# BUS.net
KiCad netlist of a schematic drawn in Altium Designer
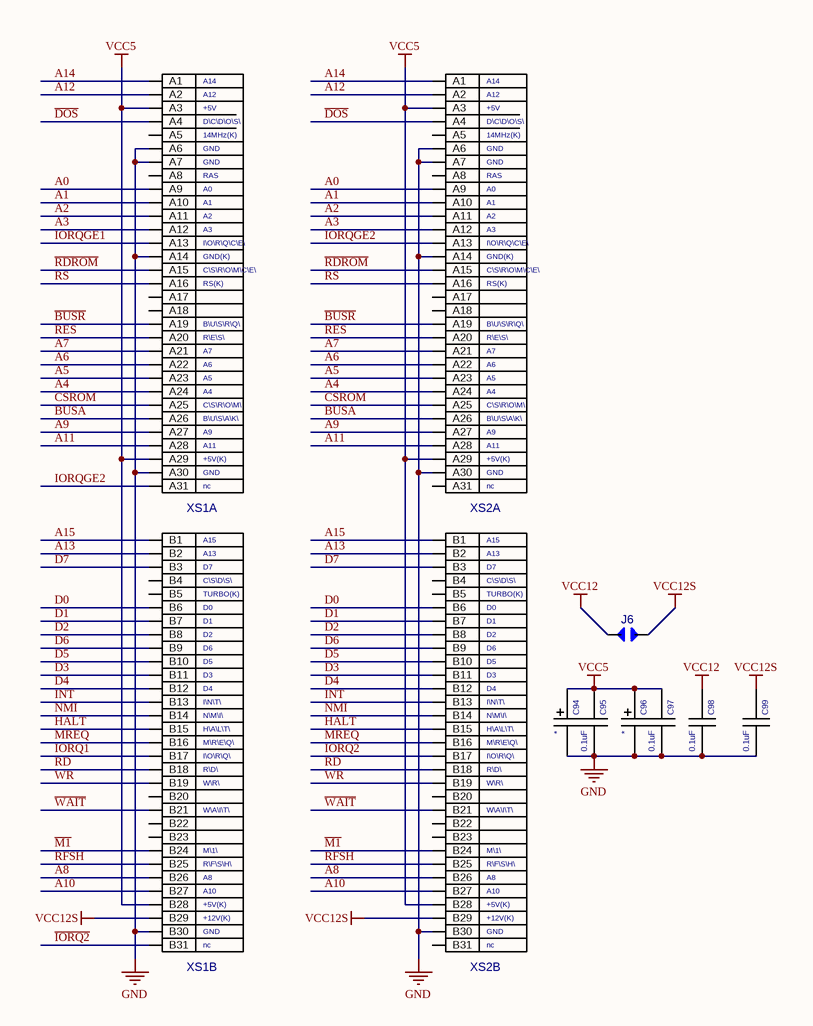
[diagram p0: BUS.SchDoc]

(export (version "E")
  (design (tool "Eeschema 10.0.6"))
  (components
    (comp (ref "C94")
      (value "ECAPCHIPB")
      (footprint "EC-CHIPB")
      (fields (field (name "ALTIUM_VALUE") "*"))
      (libsource (lib "zxevo") (part "ECAPCHIPB"))
    )
    (comp (ref "C95")
      (value "0.1uF")
      (footprint "C-CHIP")
      (description "CAPCHIP")
      (libsource (lib "*") (part "CAPCHIP"))
    )
    (comp (ref "C96")
      (value "ECAPCHIPB")
      (footprint "EC-CHIPB")
      (fields (field (name "ALTIUM_VALUE") "*"))
      (libsource (lib "zxevo") (part "ECAPCHIPB"))
    )
    (comp (ref "C97")
      (value "0.1uF")
      (footprint "C-CHIP")
      (description "CAPCHIP")
      (libsource (lib "*") (part "CAPCHIP"))
    )
    (comp (ref "C98")
      (value "0.1uF")
      (footprint "C-CHIP")
      (description "CAPCHIP")
      (libsource (lib "*") (part "CAPCHIP"))
    )
    (comp (ref "C99")
      (value "0.1uF")
      (footprint "C-CHIP")
      (description "CAPCHIP")
      (libsource (lib "*") (part "CAPCHIP"))
    )
    (comp (ref "J6")
      (value "JUMPER")
      (footprint "JUMPER")
      (description "12V enabled")
      (libsource (lib "*") (part "JUMPER"))
    )
    (comp (ref "XS1") (value "ZXSLOT") (footprint "SLOT62") (libsource (lib "*") (part "ZXSLOT")))
    (comp (ref "XS2") (value "ZXSLOT") (footprint "SLOT62") (libsource (lib "*") (part "ZXSLOT")))
  )
  (nets
    (net (code "1") (name "/A0") (class "Default")
      (node (ref "XS1") (pin "A9") (pinfunction "A9_A9") (pintype "passive"))
      (node (ref "XS2") (pin "A9") (pinfunction "A9_A9") (pintype "passive"))
    )
    (net (code "2") (name "/A1") (class "Default")
      (node (ref "XS1") (pin "A10") (pinfunction "A10_A10") (pintype "passive"))
      (node (ref "XS2") (pin "A10") (pinfunction "A10_A10") (pintype "passive"))
    )
    (net (code "3") (name "/A2") (class "Default")
      (node (ref "XS1") (pin "A11") (pinfunction "A11_A11") (pintype "passive"))
      (node (ref "XS2") (pin "A11") (pinfunction "A11_A11") (pintype "passive"))
    )
    (net (code "4") (name "/A3") (class "Default")
      (node (ref "XS1") (pin "A12") (pinfunction "A12_A12") (pintype "passive"))
      (node (ref "XS2") (pin "A12") (pinfunction "A12_A12") (pintype "passive"))
    )
    (net (code "5") (name "/A4") (class "Default")
      (node (ref "XS1") (pin "A24") (pinfunction "A24_A24") (pintype "passive"))
      (node (ref "XS2") (pin "A24") (pinfunction "A24_A24") (pintype "passive"))
    )
    (net (code "6") (name "/A5") (class "Default")
      (node (ref "XS1") (pin "A23") (pinfunction "A23_A23") (pintype "passive"))
      (node (ref "XS2") (pin "A23") (pinfunction "A23_A23") (pintype "passive"))
    )
    (net (code "7") (name "/A6") (class "Default")
      (node (ref "XS1") (pin "A22") (pinfunction "A22_A22") (pintype "passive"))
      (node (ref "XS2") (pin "A22") (pinfunction "A22_A22") (pintype "passive"))
    )
    (net (code "8") (name "/A7") (class "Default")
      (node (ref "XS1") (pin "A21") (pinfunction "A21_A21") (pintype "passive"))
      (node (ref "XS2") (pin "A21") (pinfunction "A21_A21") (pintype "passive"))
    )
    (net (code "9") (name "/A8") (class "Default")
      (node (ref "XS1") (pin "B26") (pinfunction "B26_B26") (pintype "passive"))
      (node (ref "XS2") (pin "B26") (pinfunction "B26_B26") (pintype "passive"))
    )
    (net (code "10") (name "/A9") (class "Default")
      (node (ref "XS1") (pin "A27") (pinfunction "A27_A27") (pintype "passive"))
      (node (ref "XS2") (pin "A27") (pinfunction "A27_A27") (pintype "passive"))
    )
    (net (code "11") (name "/A10") (class "Default")
      (node (ref "XS1") (pin "B27") (pinfunction "B27_B27") (pintype "passive"))
      (node (ref "XS2") (pin "B27") (pinfunction "B27_B27") (pintype "passive"))
    )
    (net (code "12") (name "/A11") (class "Default")
      (node (ref "XS1") (pin "A28") (pinfunction "A28_A28") (pintype "passive"))
      (node (ref "XS2") (pin "A28") (pinfunction "A28_A28") (pintype "passive"))
    )
    (net (code "13") (name "/A12") (class "Default")
      (node (ref "XS1") (pin "A2") (pinfunction "A2_A2") (pintype "passive"))
      (node (ref "XS2") (pin "A2") (pinfunction "A2_A2") (pintype "passive"))
    )
    (net (code "14") (name "/A13") (class "Default")
      (node (ref "XS1") (pin "B2") (pinfunction "B2_B2") (pintype "passive"))
      (node (ref "XS2") (pin "B2") (pinfunction "B2_B2") (pintype "passive"))
    )
    (net (code "15") (name "/A14") (class "Default")
      (node (ref "XS1") (pin "A1") (pinfunction "A1_A1") (pintype "passive"))
      (node (ref "XS2") (pin "A1") (pinfunction "A1_A1") (pintype "passive"))
    )
    (net (code "16") (name "/A15") (class "Default")
      (node (ref "XS1") (pin "B1") (pinfunction "B1_B1") (pintype "passive"))
      (node (ref "XS2") (pin "B1") (pinfunction "B1_B1") (pintype "passive"))
    )
    (net (code "17") (name "/D0") (class "Default")
      (node (ref "XS1") (pin "B6") (pinfunction "B6_B6") (pintype "passive"))
      (node (ref "XS2") (pin "B6") (pinfunction "B6_B6") (pintype "passive"))
    )
    (net (code "18") (name "/D1") (class "Default")
      (node (ref "XS1") (pin "B7") (pinfunction "B7_B7") (pintype "passive"))
      (node (ref "XS2") (pin "B7") (pinfunction "B7_B7") (pintype "passive"))
    )
    (net (code "19") (name "/D2") (class "Default")
      (node (ref "XS1") (pin "B8") (pinfunction "B8_B8") (pintype "passive"))
      (node (ref "XS2") (pin "B8") (pinfunction "B8_B8") (pintype "passive"))
    )
    (net (code "20") (name "/D3") (class "Default")
      (node (ref "XS1") (pin "B11") (pinfunction "B11_B11") (pintype "passive"))
      (node (ref "XS2") (pin "B11") (pinfunction "B11_B11") (pintype "passive"))
    )
    (net (code "21") (name "/D4") (class "Default")
      (node (ref "XS1") (pin "B12") (pinfunction "B12_B12") (pintype "passive"))
      (node (ref "XS2") (pin "B12") (pinfunction "B12_B12") (pintype "passive"))
    )
    (net (code "22") (name "/D5") (class "Default")
      (node (ref "XS1") (pin "B10") (pinfunction "B10_B10") (pintype "passive"))
      (node (ref "XS2") (pin "B10") (pinfunction "B10_B10") (pintype "passive"))
    )
    (net (code "23") (name "/D6") (class "Default")
      (node (ref "XS1") (pin "B9") (pinfunction "B9_B9") (pintype "passive"))
      (node (ref "XS2") (pin "B9") (pinfunction "B9_B9") (pintype "passive"))
    )
    (net (code "24") (name "/D7") (class "Default")
      (node (ref "XS1") (pin "B3") (pinfunction "B3_B3") (pintype "passive"))
      (node (ref "XS2") (pin "B3") (pinfunction "B3_B3") (pintype "passive"))
    )
    (net (code "25") (name "/IORQGE1") (class "Default")
      (node (ref "XS1") (pin "A13") (pinfunction "A13_A13") (pintype "passive"))
    )
    (net (code "26") (name "/IORQGE2") (class "Default")
      (node (ref "XS1") (pin "A31") (pinfunction "A31_A31") (pintype "passive"))
      (node (ref "XS2") (pin "A13") (pinfunction "A13_A13") (pintype "passive"))
    )
    (net (code "27") (name "/RS") (class "Default")
      (node (ref "XS1") (pin "A16") (pinfunction "A16_A16") (pintype "passive"))
      (node (ref "XS2") (pin "A16") (pinfunction "A16_A16") (pintype "passive"))
    )
    (net (code "28") (name "/~{BUSA}") (class "Default")
      (node (ref "XS1") (pin "A26") (pinfunction "A26_A26") (pintype "passive"))
      (node (ref "XS2") (pin "A26") (pinfunction "A26_A26") (pintype "passive"))
    )
    (net (code "29") (name "/~{BUSR}") (class "Default")
      (node (ref "XS1") (pin "A19") (pinfunction "A19_A19") (pintype "passive"))
      (node (ref "XS2") (pin "A19") (pinfunction "A19_A19") (pintype "passive"))
    )
    (net (code "30") (name "/~{CSROM}") (class "Default")
      (node (ref "XS1") (pin "A25") (pinfunction "A25_A25") (pintype "passive"))
      (node (ref "XS2") (pin "A25") (pinfunction "A25_A25") (pintype "passive"))
    )
    (net (code "31") (name "/~{DOS}") (class "Default")
      (node (ref "XS1") (pin "A4") (pinfunction "A4_A4") (pintype "passive"))
      (node (ref "XS2") (pin "A4") (pinfunction "A4_A4") (pintype "passive"))
    )
    (net (code "32") (name "/~{HALT}") (class "Default")
      (node (ref "XS1") (pin "B15") (pinfunction "B15_B15") (pintype "passive"))
      (node (ref "XS2") (pin "B15") (pinfunction "B15_B15") (pintype "passive"))
    )
    (net (code "33") (name "/~{INT}") (class "Default")
      (node (ref "XS1") (pin "B13") (pinfunction "B13_B13") (pintype "passive"))
      (node (ref "XS2") (pin "B13") (pinfunction "B13_B13") (pintype "passive"))
    )
    (net (code "34") (name "/~{IORQ1}") (class "Default")
      (node (ref "XS1") (pin "B17") (pinfunction "B17_B17") (pintype "passive"))
    )
    (net (code "35") (name "/~{IORQ2}") (class "Default")
      (node (ref "XS1") (pin "B31") (pinfunction "B31_B31") (pintype "passive"))
      (node (ref "XS2") (pin "B17") (pinfunction "B17_B17") (pintype "passive"))
    )
    (net (code "36") (name "/~{M1}") (class "Default")
      (node (ref "XS1") (pin "B24") (pinfunction "B24_B24") (pintype "passive"))
      (node (ref "XS2") (pin "B24") (pinfunction "B24_B24") (pintype "passive"))
    )
    (net (code "37") (name "/~{MREQ}") (class "Default")
      (node (ref "XS1") (pin "B16") (pinfunction "B16_B16") (pintype "passive"))
      (node (ref "XS2") (pin "B16") (pinfunction "B16_B16") (pintype "passive"))
    )
    (net (code "38") (name "/~{NMI}") (class "Default")
      (node (ref "XS1") (pin "B14") (pinfunction "B14_B14") (pintype "passive"))
      (node (ref "XS2") (pin "B14") (pinfunction "B14_B14") (pintype "passive"))
    )
    (net (code "39") (name "/~{RDROM}") (class "Default")
      (node (ref "XS1") (pin "A15") (pinfunction "A15_A15") (pintype "passive"))
      (node (ref "XS2") (pin "A15") (pinfunction "A15_A15") (pintype "passive"))
    )
    (net (code "40") (name "/~{RD}") (class "Default")
      (node (ref "XS1") (pin "B18") (pinfunction "B18_B18") (pintype "passive"))
      (node (ref "XS2") (pin "B18") (pinfunction "B18_B18") (pintype "passive"))
    )
    (net (code "41") (name "/~{RES}") (class "Default")
      (node (ref "XS1") (pin "A20") (pinfunction "A20_A20") (pintype "passive"))
      (node (ref "XS2") (pin "A20") (pinfunction "A20_A20") (pintype "passive"))
    )
    (net (code "42") (name "/~{RFSH}") (class "Default")
      (node (ref "XS1") (pin "B25") (pinfunction "B25_B25") (pintype "passive"))
      (node (ref "XS2") (pin "B25") (pinfunction "B25_B25") (pintype "passive"))
    )
    (net (code "43") (name "/~{WAIT}") (class "Default")
      (node (ref "XS1") (pin "B21") (pinfunction "B21_B21") (pintype "passive"))
      (node (ref "XS2") (pin "B21") (pinfunction "B21_B21") (pintype "passive"))
    )
    (net (code "44") (name "/~{WR}") (class "Default")
      (node (ref "XS1") (pin "B19") (pinfunction "B19_B19") (pintype "passive"))
      (node (ref "XS2") (pin "B19") (pinfunction "B19_B19") (pintype "passive"))
    )
    (net (code "45") (name "GND") (class "Default")
      (node (ref "C94") (pin "2") (pintype "passive"))
      (node (ref "C95") (pin "2") (pinfunction "2_2") (pintype "passive"))
      (node (ref "C96") (pin "2") (pintype "passive"))
      (node (ref "C97") (pin "2") (pinfunction "2_2") (pintype "passive"))
      (node (ref "C98") (pin "2") (pinfunction "2_2") (pintype "passive"))
      (node (ref "C99") (pin "2") (pinfunction "2_2") (pintype "passive"))
      (node (ref "XS1") (pin "A14") (pinfunction "A14_A14") (pintype "passive"))
      (node (ref "XS1") (pin "A30") (pinfunction "A30_A30") (pintype "passive"))
      (node (ref "XS1") (pin "A6") (pinfunction "A6_A6") (pintype "passive"))
      (node (ref "XS1") (pin "A7") (pinfunction "A7_A7") (pintype "passive"))
      (node (ref "XS1") (pin "B30") (pinfunction "B30_B30") (pintype "passive"))
      (node (ref "XS2") (pin "A14") (pinfunction "A14_A14") (pintype "passive"))
      (node (ref "XS2") (pin "A30") (pinfunction "A30_A30") (pintype "passive"))
      (node (ref "XS2") (pin "A6") (pinfunction "A6_A6") (pintype "passive"))
      (node (ref "XS2") (pin "A7") (pinfunction "A7_A7") (pintype "passive"))
      (node (ref "XS2") (pin "B30") (pinfunction "B30_B30") (pintype "passive"))
    )
    (net (code "46") (name "VCC5") (class "Default")
      (node (ref "C94") (pin "1") (pintype "passive"))
      (node (ref "C95") (pin "1") (pinfunction "1_1") (pintype "passive"))
      (node (ref "C96") (pin "1") (pintype "passive"))
      (node (ref "C97") (pin "1") (pinfunction "1_1") (pintype "passive"))
      (node (ref "XS1") (pin "A29") (pinfunction "A29_A29") (pintype "passive"))
      (node (ref "XS1") (pin "A3") (pinfunction "A3_A3") (pintype "passive"))
      (node (ref "XS1") (pin "B28") (pinfunction "B28_B28") (pintype "passive"))
      (node (ref "XS2") (pin "A29") (pinfunction "A29_A29") (pintype "passive"))
      (node (ref "XS2") (pin "A3") (pinfunction "A3_A3") (pintype "passive"))
      (node (ref "XS2") (pin "B28") (pinfunction "B28_B28") (pintype "passive"))
    )
    (net (code "47") (name "VCC12") (class "Default")
      (node (ref "C98") (pin "1") (pinfunction "1_1") (pintype "passive"))
      (node (ref "J6") (pin "0") (pinfunction "1_0") (pintype "passive"))
    )
    (net (code "48") (name "VCC12S") (class "Default")
      (node (ref "C99") (pin "1") (pinfunction "1_1") (pintype "passive"))
      (node (ref "J6") (pin "1") (pinfunction "2_1") (pintype "passive"))
      (node (ref "XS1") (pin "B29") (pinfunction "B29_B29") (pintype "passive"))
      (node (ref "XS2") (pin "B29") (pinfunction "B29_B29") (pintype "passive"))
    )
    (net (code "49") (name "unconnected-(XS1-PadA5)") (class "Default")
      (node (ref "XS1") (pin "A5") (pinfunction "A5_A5") (pintype "passive"))
    )
    (net (code "50") (name "unconnected-(XS1-PadA8)") (class "Default")
      (node (ref "XS1") (pin "A8") (pinfunction "A8_A8") (pintype "passive"))
    )
    (net (code "51") (name "unconnected-(XS1-PadA17)") (class "Default")
      (node (ref "XS1") (pin "A17") (pinfunction "A17_A17") (pintype "passive"))
    )
    (net (code "52") (name "unconnected-(XS1-PadA18)") (class "Default")
      (node (ref "XS1") (pin "A18") (pinfunction "A18_A18") (pintype "passive"))
    )
    (net (code "53") (name "unconnected-(XS1-PadB4)") (class "Default")
      (node (ref "XS1") (pin "B4") (pinfunction "B4_B4") (pintype "passive"))
    )
    (net (code "54") (name "unconnected-(XS1-PadB5)") (class "Default")
      (node (ref "XS1") (pin "B5") (pinfunction "B5_B5") (pintype "passive"))
    )
    (net (code "55") (name "unconnected-(XS1-PadB20)") (class "Default")
      (node (ref "XS1") (pin "B20") (pinfunction "B20_B20") (pintype "passive"))
    )
    (net (code "56") (name "unconnected-(XS1-PadB22)") (class "Default")
      (node (ref "XS1") (pin "B22") (pinfunction "B22_B22") (pintype "passive"))
    )
    (net (code "57") (name "unconnected-(XS1-PadB23)") (class "Default")
      (node (ref "XS1") (pin "B23") (pinfunction "B23_B23") (pintype "passive"))
    )
    (net (code "58") (name "unconnected-(XS2-PadA5)") (class "Default")
      (node (ref "XS2") (pin "A5") (pinfunction "A5_A5") (pintype "passive"))
    )
    (net (code "59") (name "unconnected-(XS2-PadA8)") (class "Default")
      (node (ref "XS2") (pin "A8") (pinfunction "A8_A8") (pintype "passive"))
    )
    (net (code "60") (name "unconnected-(XS2-PadA17)") (class "Default")
      (node (ref "XS2") (pin "A17") (pinfunction "A17_A17") (pintype "passive"))
    )
    (net (code "61") (name "unconnected-(XS2-PadA18)") (class "Default")
      (node (ref "XS2") (pin "A18") (pinfunction "A18_A18") (pintype "passive"))
    )
    (net (code "62") (name "unconnected-(XS2-PadA31)") (class "Default")
      (node (ref "XS2") (pin "A31") (pinfunction "A31_A31") (pintype "passive"))
    )
    (net (code "63") (name "unconnected-(XS2-PadB4)") (class "Default")
      (node (ref "XS2") (pin "B4") (pinfunction "B4_B4") (pintype "passive"))
    )
    (net (code "64") (name "unconnected-(XS2-PadB5)") (class "Default")
      (node (ref "XS2") (pin "B5") (pinfunction "B5_B5") (pintype "passive"))
    )
    (net (code "65") (name "unconnected-(XS2-PadB20)") (class "Default")
      (node (ref "XS2") (pin "B20") (pinfunction "B20_B20") (pintype "passive"))
    )
    (net (code "66") (name "unconnected-(XS2-PadB22)") (class "Default")
      (node (ref "XS2") (pin "B22") (pinfunction "B22_B22") (pintype "passive"))
    )
    (net (code "67") (name "unconnected-(XS2-PadB23)") (class "Default")
      (node (ref "XS2") (pin "B23") (pinfunction "B23_B23") (pintype "passive"))
    )
    (net (code "68") (name "unconnected-(XS2-PadB31)") (class "Default")
      (node (ref "XS2") (pin "B31") (pinfunction "B31_B31") (pintype "passive"))
    )
  )
)
